# 3_5V_Regulator.net
KiCad netlist of a schematic drawn in Altium Designer
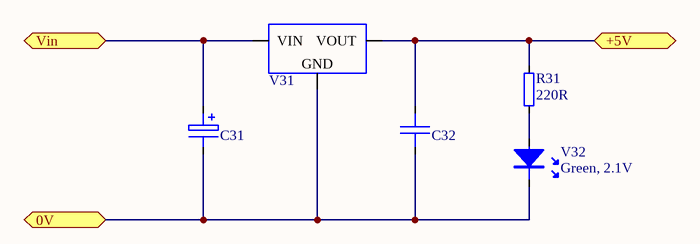
[diagram p0: 3_5V_Regulator.SchDoc]

(export (version "E")
  (design (tool "Eeschema 10.0.6"))
  (components
    (comp (ref "C31")
      (value "CAP ELEC 100u 63V 20% Radial RoHS")
      (footprint "RBP-3.5-0.8-8.0")
      (description "Capacitor Polarised")
      (fields
        (field (name "MANUFACTURER") "Panasonic")
        (field (name "PARTNUMBER") "ECA1JM101")
        (field (name "CHECKEDBY") "VHQ")
      )
      (libsource (lib "SVN_BOMGEN_Database_2014") (part "CAP-POL"))
    )
    (comp (ref "C32")
      (value "10u 50V")
      (footprint "1210")
      (description "Capacitor")
      (fields
        (field (name "MANUFACTURER") "TDK")
        (field (name "PARTNUMBER") "C3225X7S1H106K250AB")
        (field (name "CHECKEDBY") "TTX")
      )
      (libsource (lib "SVN_BOMGEN_Database_2014") (part "CAP"))
    )
    (comp (ref "R31")
      (value "220R")
      (footprint "1206")
      (description "Resistor")
      (fields
        (field (name "MANUFACTURER") "Phycomp")
        (field (name "PARTNUMBER") "RC1206FR-07220RL")
        (field (name "CHECKEDBY") "ART")
      )
      (libsource (lib "SVN_BOMGEN_Database_2014") (part "RES"))
    )
    (comp (ref "V31")
      (value "LM78L05ACZ")
      (footprint "TO92_W")
      (description "IC LM78LXX 3-terminal regulator TO92")
      (fields
        (field (name "MANUFACTURER") "TI")
        (field (name "PARTNUMBER") "LM78L05ACZ/NOPB")
        (field (name "CHECKEDBY") "pfu")
      )
      (libsource (lib "SVN_BOMGEN_Database_2014") (part "LM78LXX-TO92"))
    )
    (comp (ref "V32")
      (value "Green, 2.1V")
      (footprint "LED-0805")
      (description "LED")
      (fields
        (field (name "MANUFACTURER") "Chicago Miniature Lighting")
        (field (name "PARTNUMBER") "CMD17-21UGC/TR8")
        (field (name "CHECKEDBY") "SAA")
      )
      (libsource (lib "SVN_BOMGEN_Database_2014") (part "LED"))
    )
  )
  (nets
    (net (code "1") (name "/+5V") (class "Default")
      (node (ref "C32") (pin "1") (pinfunction "1_1") (pintype "passive"))
      (node (ref "R31") (pin "1") (pinfunction "1_1") (pintype "passive"))
      (node (ref "V31") (pin "x") (pinfunction "VOUT_x") (pintype "power_in"))
    )
    (net (code "2") (name "/0V") (class "Default")
      (node (ref "C31") (pin "-") (pinfunction "-_-") (pintype "passive"))
      (node (ref "C32") (pin "2") (pinfunction "2_2") (pintype "passive"))
      (node (ref "V31") (pin "y") (pinfunction "GND_y") (pintype "power_in"))
      (node (ref "V32") (pin "k") (pintype "passive"))
    )
    (net (code "3") (name "/Vin") (class "Default")
      (node (ref "C31") (pin "+") (pinfunction "+_+") (pintype "passive"))
      (node (ref "V31") (pin "z") (pinfunction "VIN_z") (pintype "power_in"))
    )
    (net (code "4") (name "Net-(R31-Pad2)") (class "Default")
      (node (ref "R31") (pin "2") (pinfunction "2_2") (pintype "passive"))
      (node (ref "V32") (pin "a") (pintype "passive"))
    )
  )
)
